# Main.net
KiCad netlist of a schematic drawn in Altium Designer
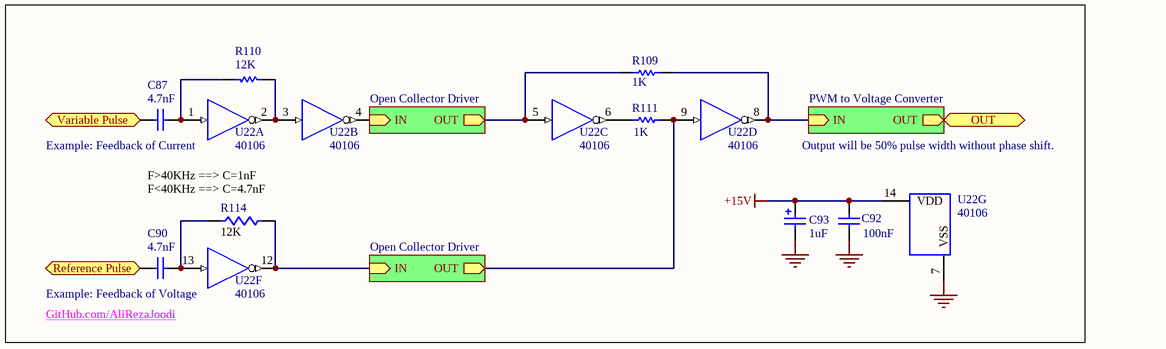
[diagram p0: Main.SchDoc]

(export (version "E")
  (design (tool "Eeschema 10.0.6"))
  (components
    (comp (ref "C87")
      (value "4.7nF")
      (footprint "RESC3216N")
      (description "Capacitor")
      (fields (field (name "Comment") "Cap") (field (name "PUBLISHER") "Altium Limited"))
      (libsource (lib "Miscellaneous Devices") (part "Cap"))
    )
    (comp (ref "C90")
      (value "4.7nF")
      (footprint "RESC3216N")
      (description "Capacitor")
      (fields
        (field (name "MANUFACTURER") "Generic Components")
        (field (name "Comment") "Cap")
        (field (name "PUBLISHER") "Altium Limited")
      )
      (libsource (lib "Miscellaneous Devices") (part "Cap"))
    )
    (comp (ref "C92")
      (value "100nF")
      (footprint "0805")
      (description "Capacitor")
      (fields (field (name "Comment") "Cap") (field (name "PUBLISHER") "Altium Limited"))
      (libsource (lib "Miscellaneous Devices") (part "Cap"))
    )
    (comp (ref "C93")
      (value "1uF")
      (footprint "Cap_A")
      (description "Polarized Capacitor (Radial)")
      (fields
        (field (name "MANUFACTURER") "Generic Components")
        (field (name "Comment") "Cap Pol1")
        (field (name "PUBLISHER") "Altium Limited")
      )
      (libsource (lib "Miscellaneous Devices") (part "Cap Pol1"))
    )
    (comp (ref "R109")
      (value "1K")
      (footprint "0805")
      (description "Resistor")
      (fields (field (name "Comment") "Res1") (field (name "PUBLISHER") "Altium Limited"))
      (libsource (lib "") (part "Res1_1"))
    )
    (comp (ref "R110")
      (value "12K")
      (footprint "0805")
      (description "Resistor")
      (fields (field (name "Comment") "Res1") (field (name "PUBLISHER") "Altium Limited"))
      (libsource (lib "") (part "Res1_1"))
    )
    (comp (ref "R111")
      (value "1K")
      (footprint "0805")
      (description "Resistor")
      (fields (field (name "Comment") "Res1") (field (name "PUBLISHER") "Altium Limited"))
      (libsource (lib "") (part "Res1_1"))
    )
    (comp (ref "R114")
      (value "12K")
      (footprint "0805")
      (description "Resistor")
      (fields
        (field (name "MANUFACTURER") "Generic Components")
        (field (name "Comment") "CAP")
        (field (name "PUBLISHER") "Altium Limited")
      )
      (libsource (lib "Miscellaneous Devices") (part "Res1"))
    )
    (comp (ref "U22")
      (value "40106")
      (footprint "SOP127P636-14N")
      (description "Hex inverting Schmitt trigger, 14-Pin")
      (fields (field (name "PUBLISHER") "Altium Limited"))
      (libsource (lib "my Libraries") (part "40106"))
    )
  )
  (nets
    (net (code "1") (name "+15V") (class "Default")
      (node (ref "C92") (pin "1") (pinfunction "1_1") (pintype "passive"))
      (node (ref "C93") (pin "1") (pinfunction "1_1") (pintype "passive"))
      (node (ref "U22") (pin "14") (pinfunction "VDD_14") (pintype "passive"))
    )
    (net (code "2") (name "/IN") (class "Default")
      (node (ref "U22") (pin "4") (pinfunction "~{O}_4") (pintype "output"))
    )
    (net (code "3") (name "/IN_1") (class "Default")
      (node (ref "R114") (pin "2") (pinfunction "2_2") (pintype "passive"))
      (node (ref "U22") (pin "12") (pinfunction "~{O}_12") (pintype "output"))
    )
    (net (code "4") (name "/IN_2") (class "Default")
      (node (ref "R109") (pin "1") (pinfunction "1_1") (pintype "passive"))
      (node (ref "U22") (pin "8") (pinfunction "~{O}_8") (pintype "output"))
    )
    (net (code "6") (name "/OUT_1") (class "Default")
      (node (ref "R109") (pin "2") (pinfunction "2_2") (pintype "passive"))
      (node (ref "U22") (pin "5") (pinfunction "I_5") (pintype "input"))
    )
    (net (code "7") (name "/OUT_2") (class "Default")
      (node (ref "R111") (pin "2") (pinfunction "2_2") (pintype "passive"))
      (node (ref "U22") (pin "9") (pinfunction "I_9") (pintype "input"))
    )
    (net (code "8") (name "/Reference Pulse") (class "Default")
      (node (ref "C90") (pin "2") (pinfunction "2_2") (pintype "passive"))
    )
    (net (code "9") (name "/Variable Pulse") (class "Default")
      (node (ref "C87") (pin "2") (pinfunction "2_2") (pintype "passive"))
    )
    (net (code "10") (name "GND") (class "Default")
      (node (ref "C92") (pin "2") (pinfunction "2_2") (pintype "passive"))
      (node (ref "C93") (pin "2") (pinfunction "2_2") (pintype "passive"))
      (node (ref "U22") (pin "7") (pinfunction "VSS_7") (pintype "power_in"))
    )
    (net (code "11") (name "Net-(U22A-I)") (class "Default")
      (node (ref "C87") (pin "1") (pinfunction "1_1") (pintype "passive"))
      (node (ref "R110") (pin "1") (pinfunction "1_1") (pintype "passive"))
      (node (ref "U22") (pin "1") (pinfunction "I_1") (pintype "input"))
    )
    (net (code "12") (name "Net-(U22A-~{O})") (class "Default")
      (node (ref "R110") (pin "2") (pinfunction "2_2") (pintype "passive"))
      (node (ref "U22") (pin "2") (pinfunction "~{O}_2") (pintype "output"))
      (node (ref "U22") (pin "3") (pinfunction "I_3") (pintype "input"))
    )
    (net (code "13") (name "Net-(U22C-~{O})") (class "Default")
      (node (ref "R111") (pin "1") (pinfunction "1_1") (pintype "passive"))
      (node (ref "U22") (pin "6") (pinfunction "~{O}_6") (pintype "output"))
    )
    (net (code "14") (name "Net-(U22F-I)") (class "Default")
      (node (ref "C90") (pin "1") (pinfunction "1_1") (pintype "passive"))
      (node (ref "R114") (pin "1") (pinfunction "1_1") (pintype "passive"))
      (node (ref "U22") (pin "13") (pinfunction "I_13") (pintype "input"))
    )
  )
)
